# DM1092_IMU.net
KiCad netlist of a schematic drawn in Altium Designer
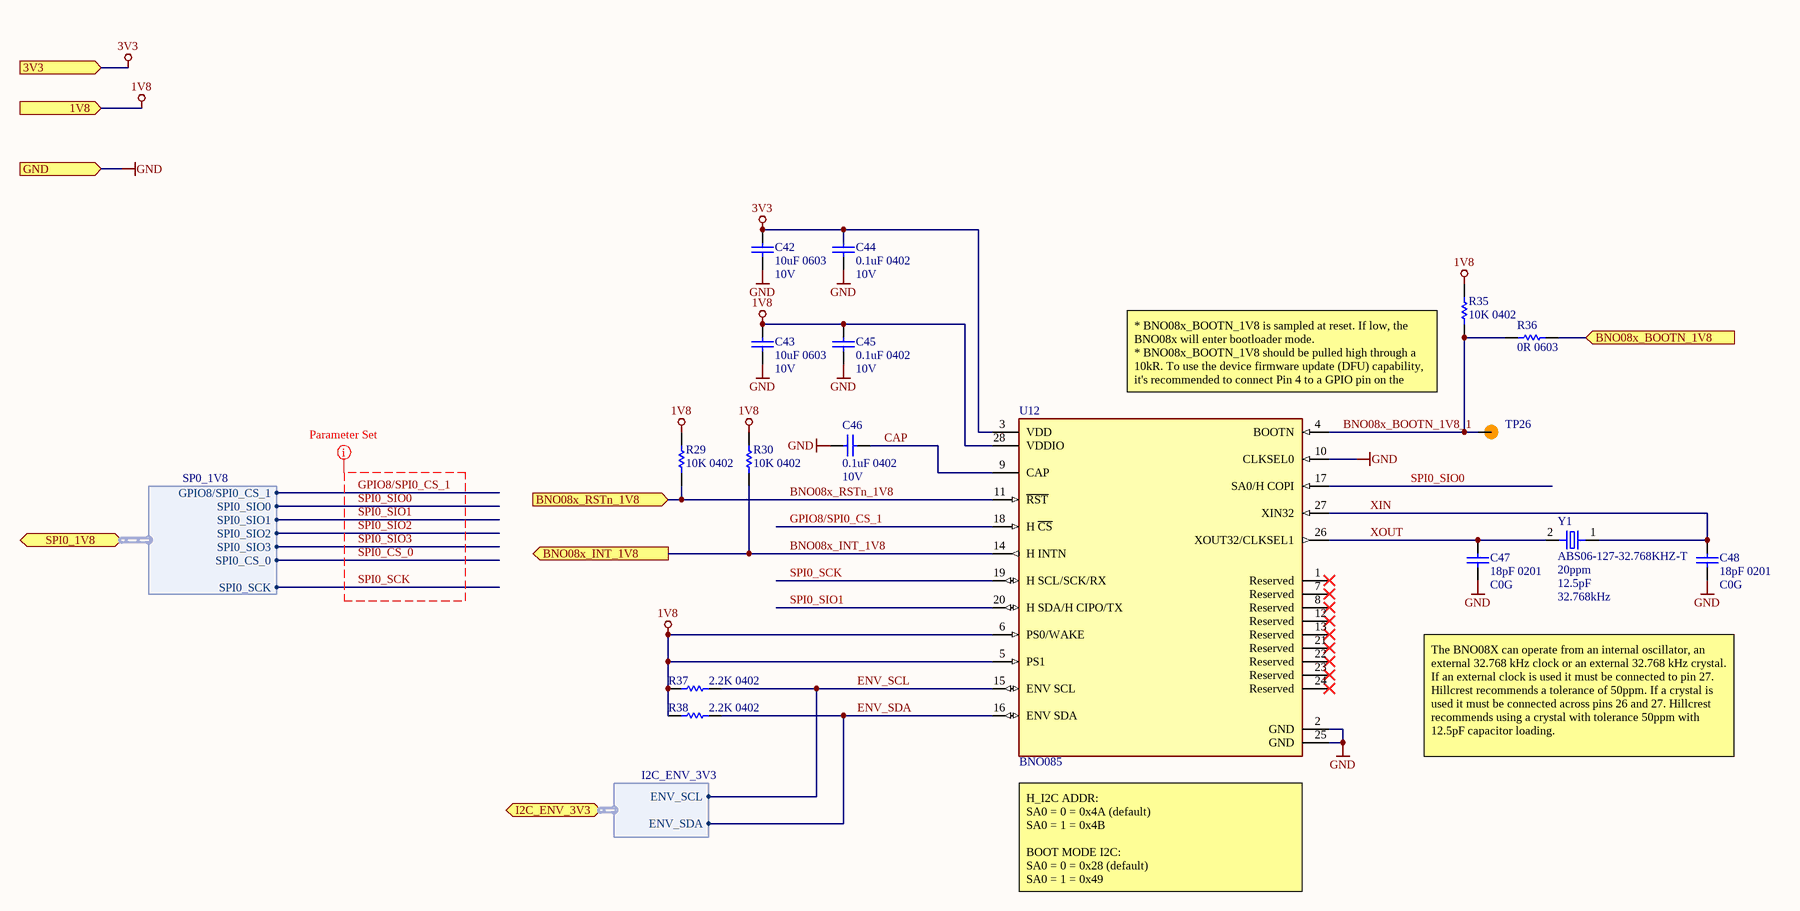
[diagram p0: DM1092_IMU.SchDoc]

(export (version "E")
  (design (tool "Eeschema 10.0.6"))
  (components
    (comp (ref "C42")
      (value "10uF 0603")
      (footprint "CAP_Altium_Vault_Generic:CAPC0603(1608)100_N")
      (description "CAP CER 10UF 10V X5R 0603 20%")
      (fields (field (name "TOLERANCE") "20%") (field (name "VOLTAGE RATING") "10V"))
      (libsource (lib "LuxonisMaster") (part "GRM188R61A106ME69D"))
    )
    (comp (ref "C43")
      (value "10uF 0603")
      (footprint "CAP_Altium_Vault_Generic:CAPC0603(1608)100_N")
      (description "CAP CER 10UF 10V X5R 0603 20%")
      (fields (field (name "TOLERANCE") "20%") (field (name "VOLTAGE RATING") "10V"))
      (libsource (lib "LuxonisMaster") (part "GRM188R61A106ME69D"))
    )
    (comp (ref "C44")
      (value "0.1uF 0402")
      (footprint "CAP_Altium_Vault_Generic:CAPC0402(1005)70_N")
      (description "CAP CER 0.1UF 10V X7R 0402 5%")
      (fields (field (name "TOLERANCE") "5%") (field (name "VOLTAGE RATING") "10V"))
      (libsource (lib "LuxonisMaster") (part "GRM155R71A104JA01D"))
    )
    (comp (ref "C45")
      (value "0.1uF 0402")
      (footprint "CAP_Altium_Vault_Generic:CAPC0402(1005)70_N")
      (description "CAP CER 0.1UF 10V X7R 0402 5%")
      (fields (field (name "TOLERANCE") "5%") (field (name "VOLTAGE RATING") "10V"))
      (libsource (lib "LuxonisMaster") (part "GRM155R71A104JA01D"))
    )
    (comp (ref "C46")
      (value "0.1uF 0402")
      (footprint "CAP_Altium_Vault_Generic:CAPC0402(1005)70_N")
      (description "CAP CER 0.1UF 10V X7R 0402 5%")
      (fields (field (name "TOLERANCE") "5%") (field (name "VOLTAGE RATING") "10V"))
      (libsource (lib "LuxonisMaster") (part "GRM155R71A104JA01D"))
    )
    (comp (ref "C47")
      (value "18pF 0201")
      (footprint "CAP_Altium_Vault_Generic:CAPC0201(0603)33_N")
      (description "Cap Ceramic 18pF 25V C0G 1% Pad SMD 0201 125C T/R")
      (fields (field (name "TOLERANCE") "1%") (field (name "DIELECTRIC") "C0G"))
      (libsource (lib "BW1092_R0M0E0") (part "GRM0335C1E180FA01D"))
    )
    (comp (ref "C48")
      (value "18pF 0201")
      (footprint "CAP_Altium_Vault_Generic:CAPC0201(0603)33_N")
      (description "Cap Ceramic 18pF 25V C0G 1% Pad SMD 0201 125C T/R")
      (fields (field (name "TOLERANCE") "1%") (field (name "DIELECTRIC") "C0G"))
      (libsource (lib "BW1092_R0M0E0") (part "GRM0335C1E180FA01D"))
    )
    (comp (ref "R29")
      (value "10K 0402")
      (footprint "RES_Altium_Vault_Generic:RESC0402(1005)_N")
      (fields (field (name "TOLERANCE") "1%"))
      (libsource (lib "LuxonisMaster") (part "RC0402FR-1310KL"))
    )
    (comp (ref "R30")
      (value "10K 0402")
      (footprint "RES_Altium_Vault_Generic:RESC0402(1005)_N")
      (fields (field (name "TOLERANCE") "1%"))
      (libsource (lib "LuxonisMaster") (part "RC0402FR-1310KL"))
    )
    (comp (ref "R35")
      (value "10K 0402")
      (footprint "RES_Altium_Vault_Generic:RESC0402(1005)_N")
      (fields (field (name "TOLERANCE") "1%"))
      (libsource (lib "LuxonisMaster") (part "RC0402FR-1310KL"))
    )
    (comp (ref "R36")
      (value "0R 0603")
      (footprint "RES_Altium_Vault_Generic:RESC0603(1608)_N")
      (fields (field (name "TOLERANCE") "5%"))
      (libsource (lib "LuxonisMaster") (part "CRCW06030000Z0EA"))
    )
    (comp (ref "R37")
      (value "2.2K 0402")
      (footprint "RES_Altium_Vault_Generic:RESC0402(1005)_N")
      (description "RES SMD 2.2K OHM 1% 1/16W 0402")
      (fields (field (name "TOLERANCE") "1%"))
      (libsource (lib "LuxonisMaster") (part "RC0402FR-072K2L"))
    )
    (comp (ref "R38")
      (value "2.2K 0402")
      (footprint "RES_Altium_Vault_Generic:RESC0402(1005)_N")
      (description "RES SMD 2.2K OHM 1% 1/16W 0402")
      (fields (field (name "TOLERANCE") "1%"))
      (libsource (lib "LuxonisMaster") (part "RC0402FR-072K2L"))
    )
    (comp (ref "TP26")
      (value "TP100_200_NS")
      (footprint "LuxonisMaster:TP100_200_NS")
      (libsource (lib "LuxonisMaster") (part "TEST_POINT"))
    )
    (comp (ref "U12")
      (value "BNO085")
      (footprint "BW1092_R0M0E0:BNO085")
      (description "IMU ACCEL/GYRO/MAG I2C 32BIT")
      (libsource (lib "BW1092_R0M0E0") (part "BNO085"))
    )
    (comp (ref "Y1")
      (value "ABS06-127-32.768KHZ-T")
      (footprint "BW1092_R0M0E0:ABS06-127-32.768KHZ-T")
      (description "CRYSTAL 32.768kHz ±20ppm Crystal 12.5pF 90 kOhms 2-SMD, No Lead")
      (fields
        (field (name "FREQUENCY TOLERANCE") "20ppm")
        (field (name "LOAD CAPACITANCE") "12.5pF")
        (field (name "FREQUENCY") "32.768kHz")
      )
      (libsource (lib "BW1092_R0M0E0") (part "ABS06-127-32.768KHZ-T"))
    )
  )
  (nets
    (net (code "3") (name "/BNO08x_BOOTN_1V8") (class "Default")
      (node (ref "R36") (pin "2") (pinfunction "2_2") (pintype "passive"))
    )
    (net (code "4") (name "/BNO08x_BOOTN_1V8_1") (class "Default")
      (node (ref "R35") (pin "1") (pinfunction "1_1") (pintype "passive"))
      (node (ref "R36") (pin "1") (pinfunction "1_1") (pintype "passive"))
      (node (ref "TP26") (pin "1") (pintype "passive"))
      (node (ref "U12") (pin "4") (pinfunction "BOOTN_4") (pintype "input"))
    )
    (net (code "5") (name "/BNO08x_INT_1V8") (class "Default")
      (node (ref "R30") (pin "1") (pinfunction "1_1") (pintype "passive"))
      (node (ref "U12") (pin "14") (pinfunction "H_INTN_14") (pintype "output"))
    )
    (net (code "6") (name "/BNO08x_RSTn_1V8") (class "Default")
      (node (ref "R29") (pin "1") (pinfunction "1_1") (pintype "passive"))
      (node (ref "U12") (pin "11") (pinfunction "~{RST}_11") (pintype "input"))
    )
    (net (code "7") (name "/CAP") (class "Default")
      (node (ref "C46") (pin "1") (pinfunction "1_1") (pintype "passive"))
      (node (ref "U12") (pin "9") (pinfunction "CAP_9") (pintype "passive"))
    )
    (net (code "8") (name "/ENV_SCL") (class "Default")
      (node (ref "R37") (pin "2") (pinfunction "2_2") (pintype "passive"))
      (node (ref "U12") (pin "15") (pinfunction "ENV_SCL_15") (pintype "bidirectional"))
    )
    (net (code "9") (name "/ENV_SDA") (class "Default")
      (node (ref "R38") (pin "2") (pinfunction "2_2") (pintype "passive"))
      (node (ref "U12") (pin "16") (pinfunction "ENV_SDA_16") (pintype "bidirectional"))
    )
    (net (code "10") (name "/GPIO8{slash}SPI0_CS_1") (class "Default")
      (node (ref "U12") (pin "18") (pinfunction "H_~{CS}_18") (pintype "input"))
    )
    (net (code "12") (name "/SPI0_SCK") (class "Default")
      (node (ref "U12") (pin "19") (pinfunction "H_SCL/SCK/RX_19") (pintype "bidirectional"))
    )
    (net (code "13") (name "/SPI0_SIO0") (class "Default")
      (node (ref "U12") (pin "17") (pinfunction "SA0/H_COPI_17") (pintype "input"))
    )
    (net (code "14") (name "/SPI0_SIO1") (class "Default")
      (node (ref "U12") (pin "20") (pinfunction "H_SDA/H_CIPO/TX_20") (pintype "bidirectional"))
    )
    (net (code "17") (name "/XIN") (class "Default")
      (node (ref "C48") (pin "2") (pinfunction "2_2") (pintype "passive"))
      (node (ref "U12") (pin "27") (pinfunction "XIN32_27") (pintype "input"))
      (node (ref "Y1") (pin "1") (pinfunction "1_1") (pintype "passive"))
    )
    (net (code "18") (name "/XOUT") (class "Default")
      (node (ref "C47") (pin "2") (pinfunction "2_2") (pintype "passive"))
      (node (ref "U12") (pin "26") (pinfunction "XOUT32/CLKSEL1_26") (pintype "output"))
      (node (ref "Y1") (pin "2") (pinfunction "2_2") (pintype "passive"))
    )
    (net (code "21") (name "1V8") (class "Default")
      (node (ref "C43") (pin "2") (pinfunction "2_2") (pintype "passive"))
      (node (ref "C45") (pin "2") (pinfunction "2_2") (pintype "passive"))
      (node (ref "R29") (pin "2") (pinfunction "2_2") (pintype "passive"))
      (node (ref "R30") (pin "2") (pinfunction "2_2") (pintype "passive"))
      (node (ref "R35") (pin "2") (pinfunction "2_2") (pintype "passive"))
      (node (ref "R37") (pin "1") (pinfunction "1_1") (pintype "passive"))
      (node (ref "R38") (pin "1") (pinfunction "1_1") (pintype "passive"))
      (node (ref "U12") (pin "28") (pinfunction "VDDIO_28") (pintype "power_in"))
      (node (ref "U12") (pin "5") (pinfunction "PS1_5") (pintype "input"))
      (node (ref "U12") (pin "6") (pinfunction "PS0/WAKE_6") (pintype "input"))
    )
    (net (code "22") (name "3V3") (class "Default")
      (node (ref "C42") (pin "2") (pinfunction "2_2") (pintype "passive"))
      (node (ref "C44") (pin "2") (pinfunction "2_2") (pintype "passive"))
      (node (ref "U12") (pin "3") (pinfunction "VDD_3") (pintype "power_in"))
    )
    (net (code "23") (name "GND") (class "Default")
      (node (ref "C42") (pin "1") (pinfunction "1_1") (pintype "passive"))
      (node (ref "C43") (pin "1") (pinfunction "1_1") (pintype "passive"))
      (node (ref "C44") (pin "1") (pinfunction "1_1") (pintype "passive"))
      (node (ref "C45") (pin "1") (pinfunction "1_1") (pintype "passive"))
      (node (ref "C46") (pin "2") (pinfunction "2_2") (pintype "passive"))
      (node (ref "C47") (pin "1") (pinfunction "1_1") (pintype "passive"))
      (node (ref "C48") (pin "1") (pinfunction "1_1") (pintype "passive"))
      (node (ref "U12") (pin "10") (pinfunction "CLKSEL0_10") (pintype "input"))
      (node (ref "U12") (pin "2") (pinfunction "GND_2") (pintype "power_in"))
      (node (ref "U12") (pin "25") (pinfunction "GND_25") (pintype "power_in"))
    )
    (net (code "24") (name "unconnected-(U12-Reserved-Pad1)") (class "Default")
      (node (ref "U12") (pin "1") (pinfunction "Reserved_1") (pintype "passive+no_connect"))
    )
    (net (code "25") (name "unconnected-(U12-Reserved-Pad7)") (class "Default")
      (node (ref "U12") (pin "7") (pinfunction "Reserved_7") (pintype "passive+no_connect"))
    )
    (net (code "26") (name "unconnected-(U12-Reserved-Pad8)") (class "Default")
      (node (ref "U12") (pin "8") (pinfunction "Reserved_8") (pintype "passive+no_connect"))
    )
    (net (code "27") (name "unconnected-(U12-Reserved-Pad12)") (class "Default")
      (node (ref "U12") (pin "12") (pinfunction "Reserved_12") (pintype "passive+no_connect"))
    )
    (net (code "28") (name "unconnected-(U12-Reserved-Pad13)") (class "Default")
      (node (ref "U12") (pin "13") (pinfunction "Reserved_13") (pintype "passive+no_connect"))
    )
    (net (code "29") (name "unconnected-(U12-Reserved-Pad21)") (class "Default")
      (node (ref "U12") (pin "21") (pinfunction "Reserved_21") (pintype "passive+no_connect"))
    )
    (net (code "30") (name "unconnected-(U12-Reserved-Pad22)") (class "Default")
      (node (ref "U12") (pin "22") (pinfunction "Reserved_22") (pintype "passive+no_connect"))
    )
    (net (code "31") (name "unconnected-(U12-Reserved-Pad23)") (class "Default")
      (node (ref "U12") (pin "23") (pinfunction "Reserved_23") (pintype "passive+no_connect"))
    )
    (net (code "32") (name "unconnected-(U12-Reserved-Pad24)") (class "Default")
      (node (ref "U12") (pin "24") (pinfunction "Reserved_24") (pintype "passive+no_connect"))
    )
  )
)
